# BP_protection_board.net
KiCad netlist of a schematic drawn in EAGLE
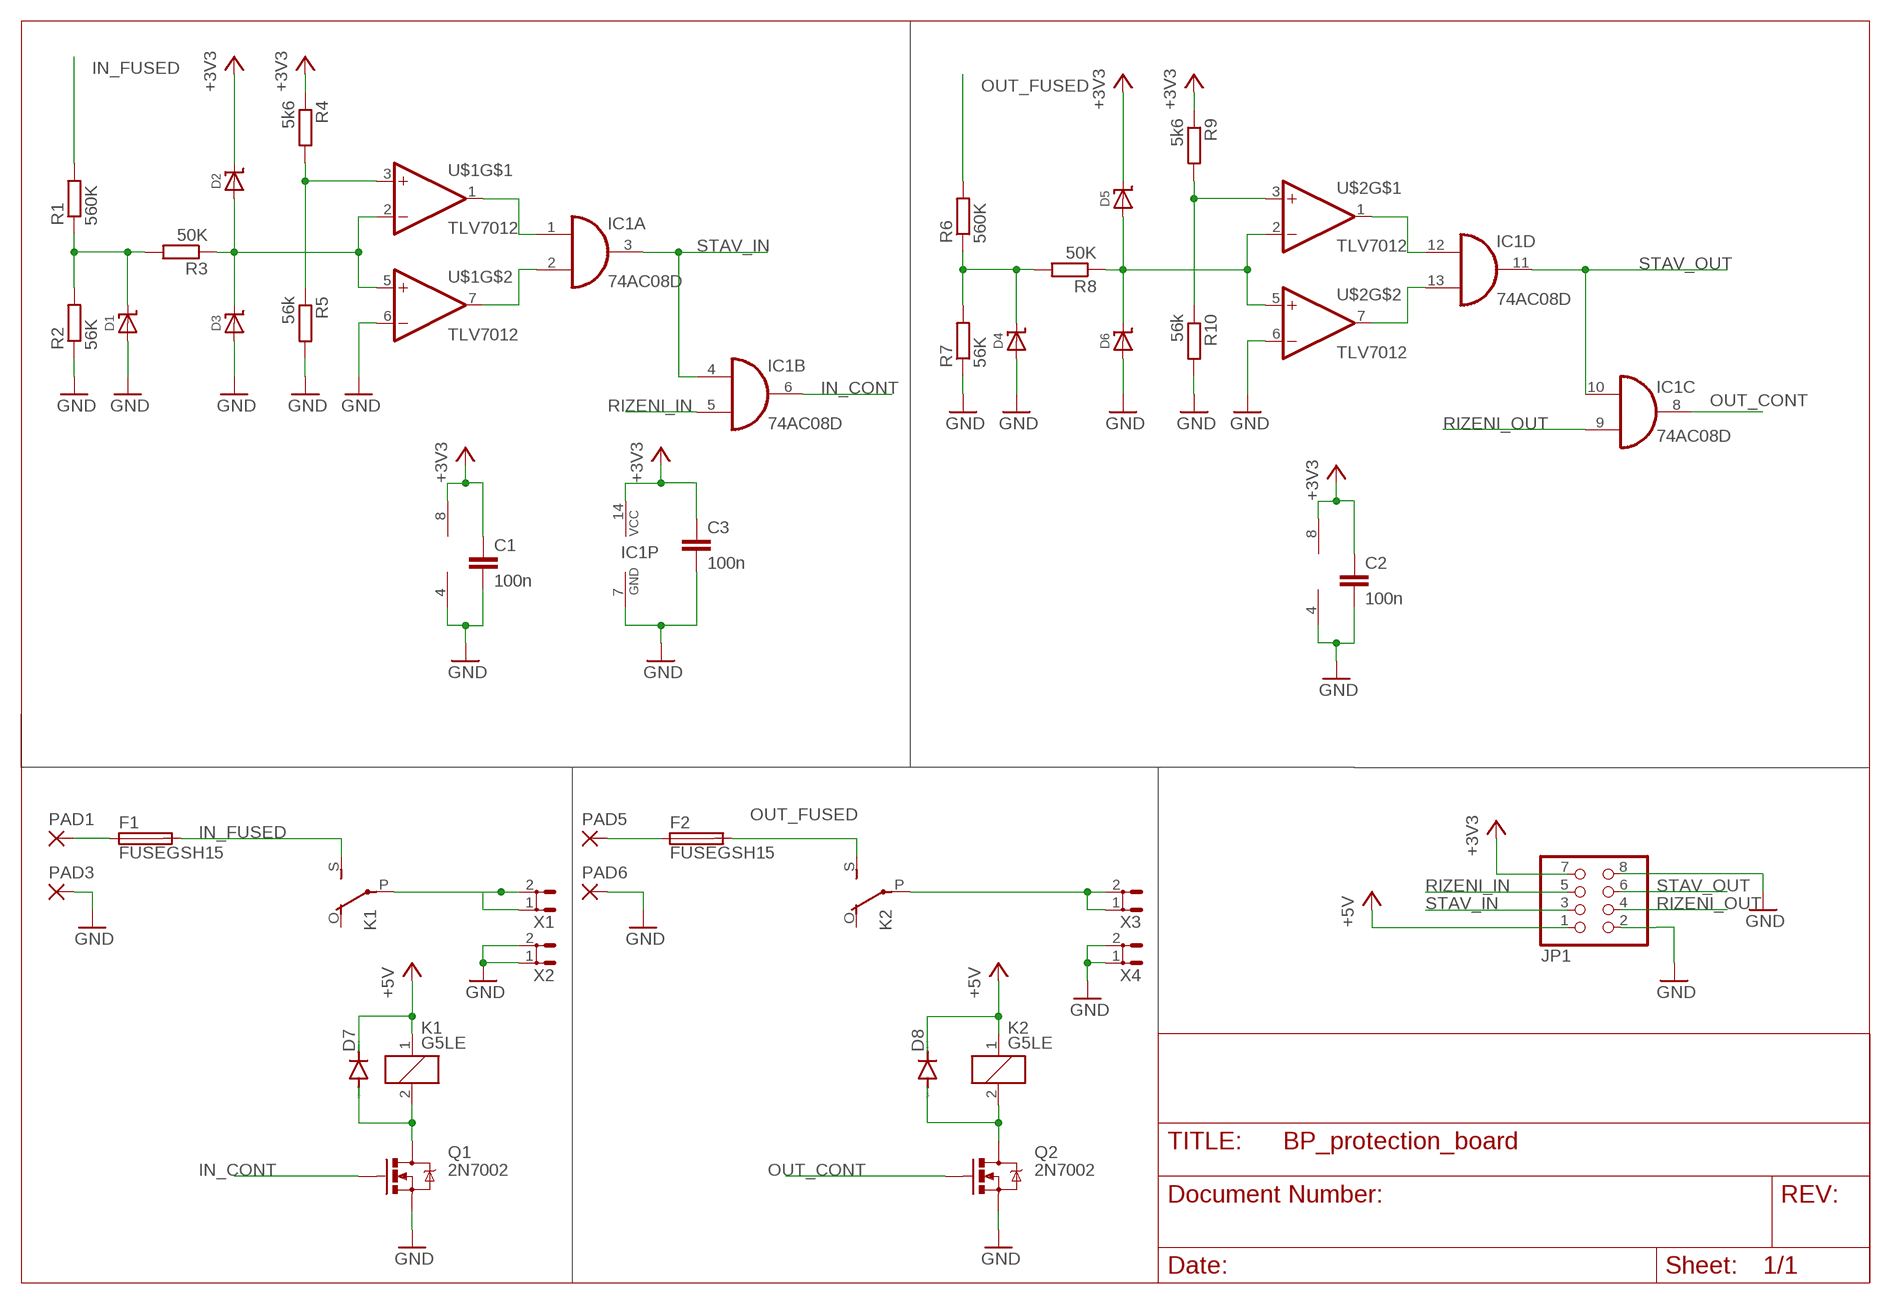
[diagram p0: schematic, sheet 1]

(export (version "E")
  (design (tool "Eeschema 10.0.6"))
  (components
    (comp (ref "C1")
      (value "100n")
      (footprint "eagle-import:C0805")
      (libsource (lib "eagle-import") (part "C-EUC0805"))
    )
    (comp (ref "C2")
      (value "100n")
      (footprint "eagle-import:C0805")
      (libsource (lib "eagle-import") (part "C-EUC0805"))
    )
    (comp (ref "C3")
      (value "100n")
      (footprint "eagle-import:C0805")
      (libsource (lib "eagle-import") (part "C-EUC0805"))
    )
    (comp (ref "D1")
      (value "DIODE-SCHOTTKYSOD-123")
      (footprint "eagle-import:SOD-123")
      (libsource (lib "eagle-import") (part "DIODE-SCHOTTKYSOD-123"))
    )
    (comp (ref "D2")
      (value "DIODE-SCHOTTKYSOD-123")
      (footprint "eagle-import:SOD-123")
      (libsource (lib "eagle-import") (part "DIODE-SCHOTTKYSOD-123"))
    )
    (comp (ref "D3")
      (value "DIODE-SCHOTTKYSOD-123")
      (footprint "eagle-import:SOD-123")
      (libsource (lib "eagle-import") (part "DIODE-SCHOTTKYSOD-123"))
    )
    (comp (ref "D4")
      (value "DIODE-SCHOTTKYSOD-123")
      (footprint "eagle-import:SOD-123")
      (libsource (lib "eagle-import") (part "DIODE-SCHOTTKYSOD-123"))
    )
    (comp (ref "D5")
      (value "DIODE-SCHOTTKYSOD-123")
      (footprint "eagle-import:SOD-123")
      (libsource (lib "eagle-import") (part "DIODE-SCHOTTKYSOD-123"))
    )
    (comp (ref "D6")
      (value "DIODE-SCHOTTKYSOD-123")
      (footprint "eagle-import:SOD-123")
      (libsource (lib "eagle-import") (part "DIODE-SCHOTTKYSOD-123"))
    )
    (comp (ref "D7")
      (value "DIODE-MELF-MLL41")
      (footprint "eagle-import:MELF-MLL41")
      (libsource (lib "eagle-import") (part "DIODE-MELF-MLL41"))
    )
    (comp (ref "D8")
      (value "DIODE-MELF-MLL41")
      (footprint "eagle-import:MELF-MLL41")
      (libsource (lib "eagle-import") (part "DIODE-MELF-MLL41"))
    )
    (comp (ref "F1")
      (value "FUSEGSH15")
      (footprint "eagle-import:GSH15")
      (libsource (lib "eagle-import") (part "FUSEGSH15"))
    )
    (comp (ref "F2")
      (value "FUSEGSH15")
      (footprint "eagle-import:GSH15")
      (libsource (lib "eagle-import") (part "FUSEGSH15"))
    )
    (comp (ref "IC1")
      (value "74AC08D")
      (footprint "eagle-import:SO14")
      (libsource (lib "eagle-import") (part "7408DAC"))
    )
    (comp (ref "JP1")
      (value "PINHD-2X4")
      (footprint "eagle-import:2X04")
      (libsource (lib "eagle-import") (part "PINHD-2X4"))
    )
    (comp (ref "K1")
      (value "G5LE")
      (footprint "eagle-import:G5LE")
      (libsource (lib "eagle-import") (part "G5LE"))
    )
    (comp (ref "K2")
      (value "G5LE")
      (footprint "eagle-import:G5LE")
      (libsource (lib "eagle-import") (part "G5LE"))
    )
    (comp (ref "PAD1")
      (value "2,54/1,0")
      (footprint "eagle-import:2,54_1,0")
      (libsource (lib "eagle-import") (part "2,54/1,0"))
    )
    (comp (ref "PAD3")
      (value "2,54/1,0")
      (footprint "eagle-import:2,54_1,0")
      (libsource (lib "eagle-import") (part "2,54/1,0"))
    )
    (comp (ref "PAD5")
      (value "2,54/1,0")
      (footprint "eagle-import:2,54_1,0")
      (libsource (lib "eagle-import") (part "2,54/1,0"))
    )
    (comp (ref "PAD6")
      (value "2,54/1,0")
      (footprint "eagle-import:2,54_1,0")
      (libsource (lib "eagle-import") (part "2,54/1,0"))
    )
    (comp (ref "Q1")
      (value "2N7002")
      (footprint "eagle-import:SOT323")
      (libsource (lib "eagle-import") (part "MOSFET-NCHANNEL2N7002PW"))
    )
    (comp (ref "Q2")
      (value "2N7002")
      (footprint "eagle-import:SOT323")
      (libsource (lib "eagle-import") (part "MOSFET-NCHANNEL2N7002PW"))
    )
    (comp (ref "R1")
      (value "560K")
      (footprint "eagle-import:R0805")
      (libsource (lib "eagle-import") (part "R-EU_R0805"))
    )
    (comp (ref "R2")
      (value "56K")
      (footprint "eagle-import:R0805")
      (libsource (lib "eagle-import") (part "R-EU_R0805"))
    )
    (comp (ref "R3")
      (value "50K")
      (footprint "eagle-import:R0805")
      (libsource (lib "eagle-import") (part "R-EU_R0805"))
    )
    (comp (ref "R4")
      (value "5k6")
      (footprint "eagle-import:R0805")
      (libsource (lib "eagle-import") (part "R-EU_R0805"))
    )
    (comp (ref "R5")
      (value "56k")
      (footprint "eagle-import:R0805")
      (libsource (lib "eagle-import") (part "R-EU_R0805"))
    )
    (comp (ref "R6")
      (value "560K")
      (footprint "eagle-import:R0805")
      (libsource (lib "eagle-import") (part "R-EU_R0805"))
    )
    (comp (ref "R7")
      (value "56K")
      (footprint "eagle-import:R0805")
      (libsource (lib "eagle-import") (part "R-EU_R0805"))
    )
    (comp (ref "R8")
      (value "50K")
      (footprint "eagle-import:R0805")
      (libsource (lib "eagle-import") (part "R-EU_R0805"))
    )
    (comp (ref "R9")
      (value "5k6")
      (footprint "eagle-import:R0805")
      (libsource (lib "eagle-import") (part "R-EU_R0805"))
    )
    (comp (ref "R10")
      (value "56k")
      (footprint "eagle-import:R0805")
      (libsource (lib "eagle-import") (part "R-EU_R0805"))
    )
    (comp (ref "U$1")
      (value "TLV7012")
      (footprint "eagle-import:SOT-23-THIN")
      (libsource (lib "eagle-import") (part "TLV7012"))
    )
    (comp (ref "U$2")
      (value "TLV7012")
      (footprint "eagle-import:SOT-23-THIN")
      (libsource (lib "eagle-import") (part "TLV7012"))
    )
    (comp (ref "X1")
      (value "ST6,3")
      (footprint "eagle-import:ST6,3")
      (libsource (lib "eagle-import") (part "ST6,3"))
    )
    (comp (ref "X2")
      (value "ST6,3")
      (footprint "eagle-import:ST6,3")
      (libsource (lib "eagle-import") (part "ST6,3"))
    )
    (comp (ref "X3")
      (value "ST6,3")
      (footprint "eagle-import:ST6,3")
      (libsource (lib "eagle-import") (part "ST6,3"))
    )
    (comp (ref "X4")
      (value "ST6,3")
      (footprint "eagle-import:ST6,3")
      (libsource (lib "eagle-import") (part "ST6,3"))
    )
  )
  (nets
    (net (code "1") (name "+3V3") (class "Default")
      (node (ref "C1") (pin "1") (pinfunction "1_1") (pintype "passive"))
      (node (ref "C2") (pin "1") (pinfunction "1_1") (pintype "passive"))
      (node (ref "C3") (pin "1") (pinfunction "1_1") (pintype "passive"))
      (node (ref "D2") (pin "C") (pinfunction "C_C") (pintype "passive"))
      (node (ref "D5") (pin "C") (pinfunction "C_C") (pintype "passive"))
      (node (ref "IC1") (pin "14") (pinfunction "VCC_14") (pintype "power_in"))
      (node (ref "JP1") (pin "7") (pinfunction "7_7") (pintype "passive"))
      (node (ref "R4") (pin "1") (pinfunction "1_1") (pintype "passive"))
      (node (ref "R9") (pin "1") (pinfunction "1_1") (pintype "passive"))
      (node (ref "U$1") (pin "8") (pinfunction "V+_8") (pintype "power_in"))
      (node (ref "U$2") (pin "8") (pinfunction "V+_8") (pintype "power_in"))
    )
    (net (code "2") (name "+5V") (class "Default")
      (node (ref "D7") (pin "C") (pinfunction "C_C") (pintype "passive"))
      (node (ref "D8") (pin "C") (pinfunction "C_C") (pintype "passive"))
      (node (ref "JP1") (pin "1") (pinfunction "1_1") (pintype "passive"))
      (node (ref "K1") (pin "1") (pinfunction "1_1") (pintype "passive"))
      (node (ref "K2") (pin "1") (pinfunction "1_1") (pintype "passive"))
    )
    (net (code "3") (name "/IN_CONT") (class "Default")
      (node (ref "IC1") (pin "6") (pinfunction "O_6") (pintype "output"))
      (node (ref "Q1") (pin "1") (pinfunction "G_1") (pintype "passive"))
    )
    (net (code "4") (name "/IN_FUSED") (class "Default")
      (node (ref "F1") (pin "2") (pinfunction "2_2") (pintype "passive"))
      (node (ref "K1") (pin "S") (pinfunction "S_S") (pintype "passive"))
      (node (ref "R1") (pin "2") (pinfunction "2_2") (pintype "passive"))
    )
    (net (code "5") (name "/OUT_CONT") (class "Default")
      (node (ref "IC1") (pin "8") (pinfunction "O_8") (pintype "output"))
      (node (ref "Q2") (pin "1") (pinfunction "G_1") (pintype "passive"))
    )
    (net (code "6") (name "/OUT_FUSED") (class "Default")
      (node (ref "F2") (pin "2") (pinfunction "2_2") (pintype "passive"))
      (node (ref "K2") (pin "S") (pinfunction "S_S") (pintype "passive"))
      (node (ref "R6") (pin "2") (pinfunction "2_2") (pintype "passive"))
    )
    (net (code "7") (name "/RIZENI_IN") (class "Default")
      (node (ref "IC1") (pin "5") (pinfunction "I1_5") (pintype "input"))
      (node (ref "JP1") (pin "5") (pinfunction "5_5") (pintype "passive"))
    )
    (net (code "8") (name "/RIZENI_OUT") (class "Default")
      (node (ref "IC1") (pin "9") (pinfunction "I0_9") (pintype "input"))
      (node (ref "JP1") (pin "4") (pinfunction "4_4") (pintype "passive"))
    )
    (net (code "9") (name "/STAV_IN") (class "Default")
      (node (ref "IC1") (pin "3") (pinfunction "O_3") (pintype "output"))
      (node (ref "IC1") (pin "4") (pinfunction "I0_4") (pintype "input"))
      (node (ref "JP1") (pin "3") (pinfunction "3_3") (pintype "passive"))
    )
    (net (code "10") (name "/STAV_OUT") (class "Default")
      (node (ref "IC1") (pin "10") (pinfunction "I1_10") (pintype "input"))
      (node (ref "IC1") (pin "11") (pinfunction "O_11") (pintype "output"))
      (node (ref "JP1") (pin "6") (pinfunction "6_6") (pintype "passive"))
    )
    (net (code "11") (name "GND") (class "Default")
      (node (ref "C1") (pin "2") (pinfunction "2_2") (pintype "passive"))
      (node (ref "C2") (pin "2") (pinfunction "2_2") (pintype "passive"))
      (node (ref "C3") (pin "2") (pinfunction "2_2") (pintype "passive"))
      (node (ref "D1") (pin "A") (pinfunction "A_A") (pintype "passive"))
      (node (ref "D3") (pin "A") (pinfunction "A_A") (pintype "passive"))
      (node (ref "D4") (pin "A") (pinfunction "A_A") (pintype "passive"))
      (node (ref "D6") (pin "A") (pinfunction "A_A") (pintype "passive"))
      (node (ref "IC1") (pin "7") (pinfunction "GND_7") (pintype "power_in"))
      (node (ref "JP1") (pin "2") (pinfunction "2_2") (pintype "passive"))
      (node (ref "JP1") (pin "8") (pinfunction "8_8") (pintype "passive"))
      (node (ref "PAD3") (pin "1") (pinfunction "P_1") (pintype "passive"))
      (node (ref "PAD6") (pin "1") (pinfunction "P_1") (pintype "passive"))
      (node (ref "Q1") (pin "2") (pinfunction "S_2") (pintype "passive"))
      (node (ref "Q2") (pin "2") (pinfunction "S_2") (pintype "passive"))
      (node (ref "R10") (pin "2") (pinfunction "2_2") (pintype "passive"))
      (node (ref "R2") (pin "1") (pinfunction "1_1") (pintype "passive"))
      (node (ref "R5") (pin "2") (pinfunction "2_2") (pintype "passive"))
      (node (ref "R7") (pin "1") (pinfunction "1_1") (pintype "passive"))
      (node (ref "U$1") (pin "4") (pinfunction "V-_4") (pintype "power_in"))
      (node (ref "U$1") (pin "6") (pinfunction "-IN_6") (pintype "input"))
      (node (ref "U$2") (pin "4") (pinfunction "V-_4") (pintype "power_in"))
      (node (ref "U$2") (pin "6") (pinfunction "-IN_6") (pintype "input"))
      (node (ref "X2") (pin "1") (pinfunction "1_1") (pintype "passive"))
      (node (ref "X2") (pin "2") (pinfunction "2_2") (pintype "passive"))
      (node (ref "X4") (pin "1") (pinfunction "1_1") (pintype "passive"))
      (node (ref "X4") (pin "2") (pinfunction "2_2") (pintype "passive"))
    )
    (net (code "12") (name "Net-(D1-PadC)") (class "Default")
      (node (ref "D1") (pin "C") (pinfunction "C_C") (pintype "passive"))
      (node (ref "R1") (pin "1") (pinfunction "1_1") (pintype "passive"))
      (node (ref "R2") (pin "2") (pinfunction "2_2") (pintype "passive"))
      (node (ref "R3") (pin "2") (pinfunction "2_2") (pintype "passive"))
    )
    (net (code "13") (name "Net-(D4-PadC)") (class "Default")
      (node (ref "D4") (pin "C") (pinfunction "C_C") (pintype "passive"))
      (node (ref "R6") (pin "1") (pinfunction "1_1") (pintype "passive"))
      (node (ref "R7") (pin "2") (pinfunction "2_2") (pintype "passive"))
      (node (ref "R8") (pin "2") (pinfunction "2_2") (pintype "passive"))
    )
    (net (code "14") (name "Net-(IC1A-I0)") (class "Default")
      (node (ref "IC1") (pin "1") (pinfunction "I0_1") (pintype "input"))
      (node (ref "U$1") (pin "1") (pinfunction "OUT_1") (pintype "output"))
    )
    (net (code "15") (name "Net-(IC1A-I1)") (class "Default")
      (node (ref "IC1") (pin "2") (pinfunction "I1_2") (pintype "input"))
      (node (ref "U$1") (pin "7") (pinfunction "OUT_7") (pintype "output"))
    )
    (net (code "16") (name "Net-(IC1D-I0)") (class "Default")
      (node (ref "IC1") (pin "12") (pinfunction "I0_12") (pintype "input"))
      (node (ref "U$2") (pin "1") (pinfunction "OUT_1") (pintype "output"))
    )
    (net (code "17") (name "Net-(IC1D-I1)") (class "Default")
      (node (ref "IC1") (pin "13") (pinfunction "I1_13") (pintype "input"))
      (node (ref "U$2") (pin "7") (pinfunction "OUT_7") (pintype "output"))
    )
    (net (code "18") (name "Net-(K1-PadP)") (class "Default")
      (node (ref "K1") (pin "P") (pinfunction "P_P") (pintype "passive"))
      (node (ref "X1") (pin "1") (pinfunction "1_1") (pintype "passive"))
      (node (ref "X1") (pin "2") (pinfunction "2_2") (pintype "passive"))
    )
    (net (code "19") (name "Net-(K2-PadP)") (class "Default")
      (node (ref "K2") (pin "P") (pinfunction "P_P") (pintype "passive"))
      (node (ref "X3") (pin "1") (pinfunction "1_1") (pintype "passive"))
      (node (ref "X3") (pin "2") (pinfunction "2_2") (pintype "passive"))
    )
    (net (code "20") (name "Net-(PAD1-P)") (class "Default")
      (node (ref "F1") (pin "1") (pinfunction "1_1") (pintype "passive"))
      (node (ref "PAD1") (pin "1") (pinfunction "P_1") (pintype "passive"))
    )
    (net (code "21") (name "Net-(PAD5-P)") (class "Default")
      (node (ref "F2") (pin "1") (pinfunction "1_1") (pintype "passive"))
      (node (ref "PAD5") (pin "1") (pinfunction "P_1") (pintype "passive"))
    )
    (net (code "22") (name "Net-(Q1-D)") (class "Default")
      (node (ref "D7") (pin "A") (pinfunction "A_A") (pintype "passive"))
      (node (ref "K1") (pin "2") (pinfunction "2_2") (pintype "passive"))
      (node (ref "Q1") (pin "3") (pinfunction "D_3") (pintype "passive"))
    )
    (net (code "23") (name "Net-(Q2-D)") (class "Default")
      (node (ref "D8") (pin "A") (pinfunction "A_A") (pintype "passive"))
      (node (ref "K2") (pin "2") (pinfunction "2_2") (pintype "passive"))
      (node (ref "Q2") (pin "3") (pinfunction "D_3") (pintype "passive"))
    )
    (net (code "24") (name "Net-(U$1A-+IN)") (class "Default")
      (node (ref "R4") (pin "2") (pinfunction "2_2") (pintype "passive"))
      (node (ref "R5") (pin "1") (pinfunction "1_1") (pintype "passive"))
      (node (ref "U$1") (pin "3") (pinfunction "+IN_3") (pintype "input"))
    )
    (net (code "25") (name "Net-(U$1A--IN)") (class "Default")
      (node (ref "D2") (pin "A") (pinfunction "A_A") (pintype "passive"))
      (node (ref "D3") (pin "C") (pinfunction "C_C") (pintype "passive"))
      (node (ref "R3") (pin "1") (pinfunction "1_1") (pintype "passive"))
      (node (ref "U$1") (pin "2") (pinfunction "-IN_2") (pintype "input"))
      (node (ref "U$1") (pin "5") (pinfunction "+IN_5") (pintype "input"))
    )
    (net (code "26") (name "Net-(U$2A-+IN)") (class "Default")
      (node (ref "R10") (pin "1") (pinfunction "1_1") (pintype "passive"))
      (node (ref "R9") (pin "2") (pinfunction "2_2") (pintype "passive"))
      (node (ref "U$2") (pin "3") (pinfunction "+IN_3") (pintype "input"))
    )
    (net (code "27") (name "Net-(U$2A--IN)") (class "Default")
      (node (ref "D5") (pin "A") (pinfunction "A_A") (pintype "passive"))
      (node (ref "D6") (pin "C") (pinfunction "C_C") (pintype "passive"))
      (node (ref "R8") (pin "1") (pinfunction "1_1") (pintype "passive"))
      (node (ref "U$2") (pin "2") (pinfunction "-IN_2") (pintype "input"))
      (node (ref "U$2") (pin "5") (pinfunction "+IN_5") (pintype "input"))
    )
    (net (code "28") (name "unconnected-(K1-PadO)") (class "Default")
      (node (ref "K1") (pin "O") (pinfunction "O_O") (pintype "passive"))
    )
    (net (code "29") (name "unconnected-(K2-PadO)") (class "Default")
      (node (ref "K2") (pin "O") (pinfunction "O_O") (pintype "passive"))
    )
  )
)
